# hybrid_lower_pcb3_1.net
KiCad netlist of a schematic drawn in EAGLE
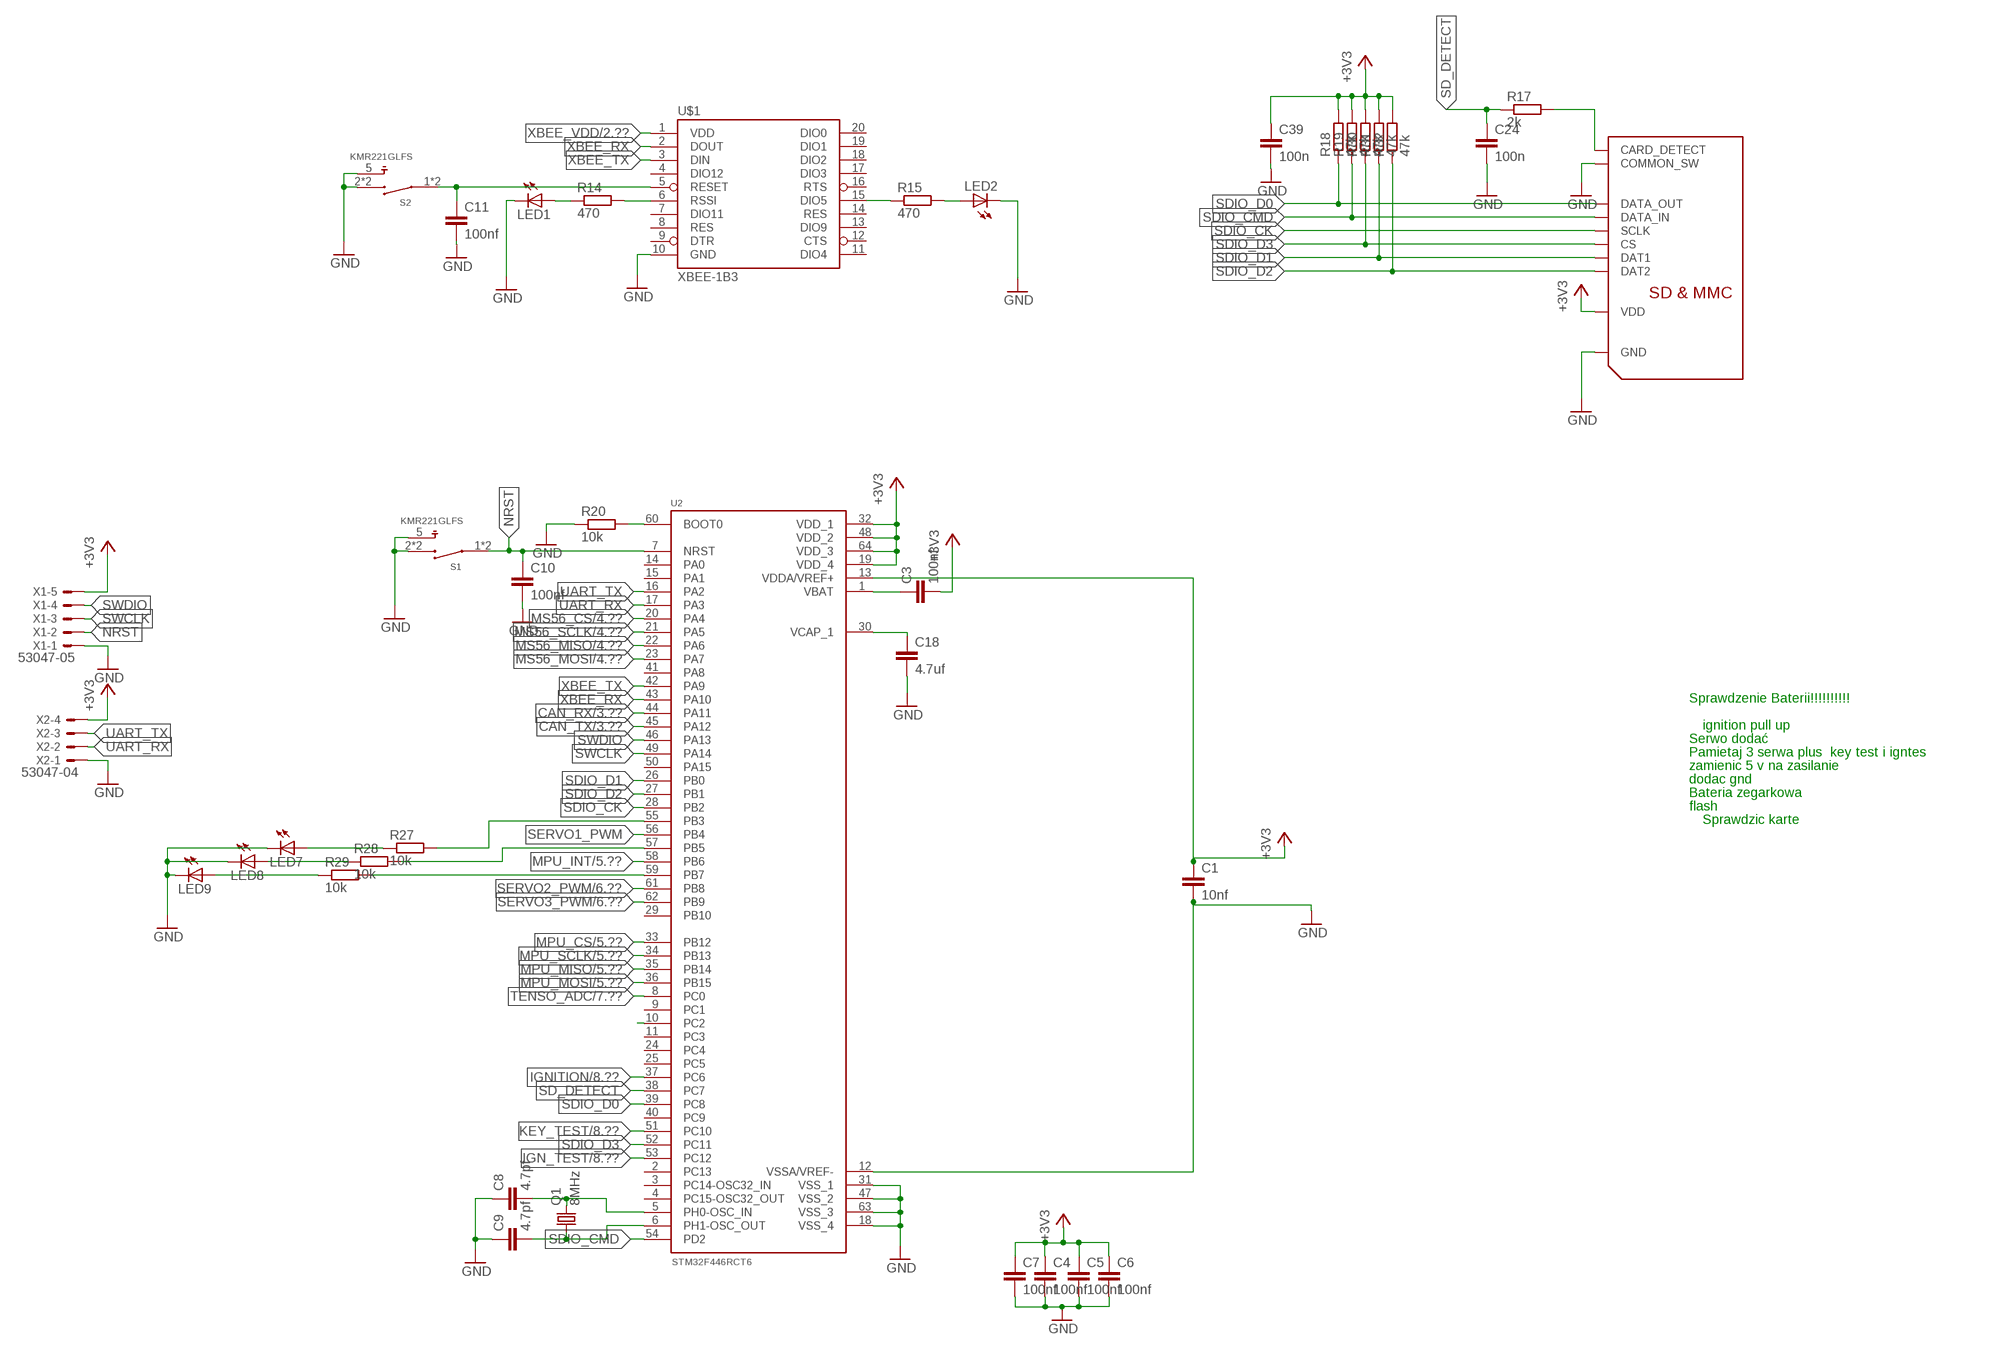
[diagram p0: schematic, sheet 1]
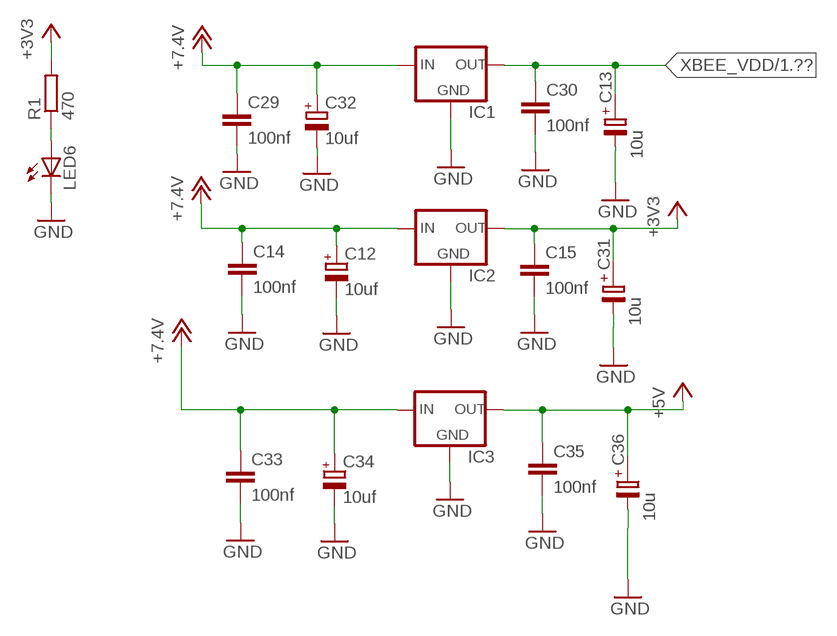
[diagram p1: schematic, sheet 2]
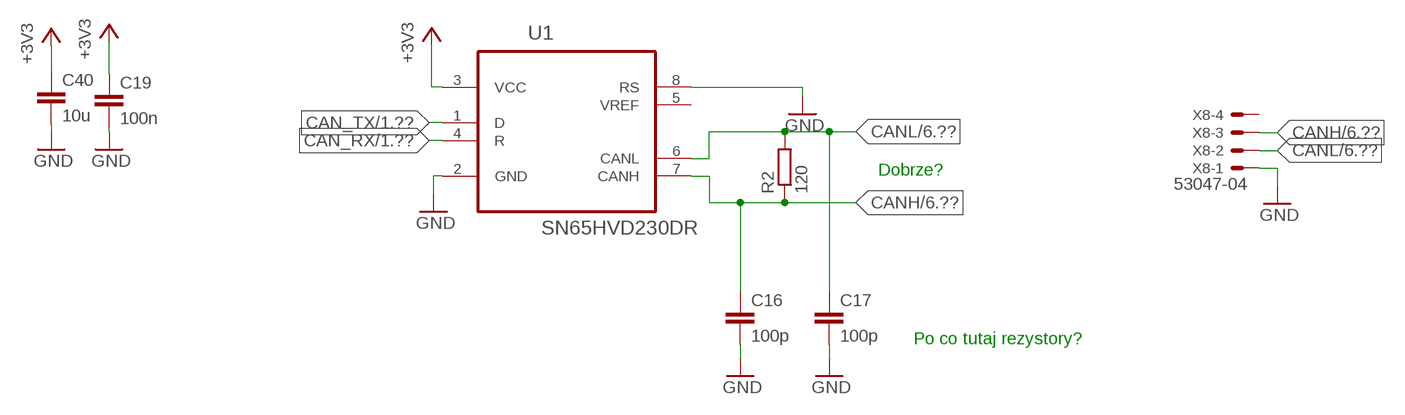
[diagram p2: schematic, sheet 3]
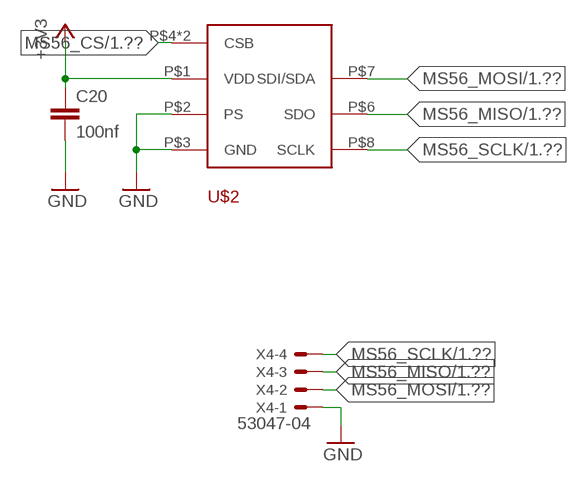
[diagram p3: schematic, sheet 4]
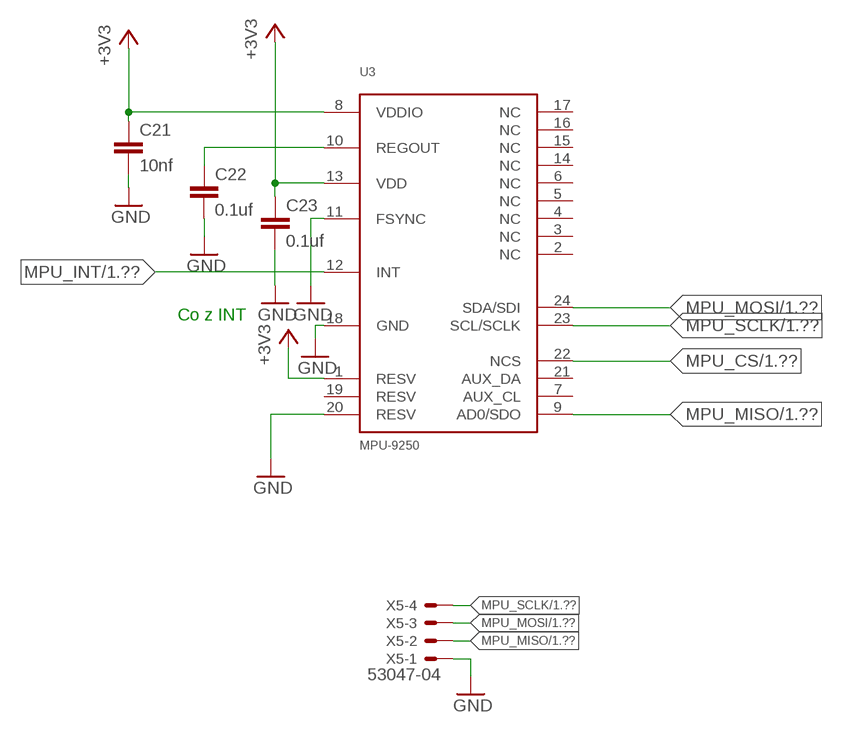
[diagram p4: schematic, sheet 5]
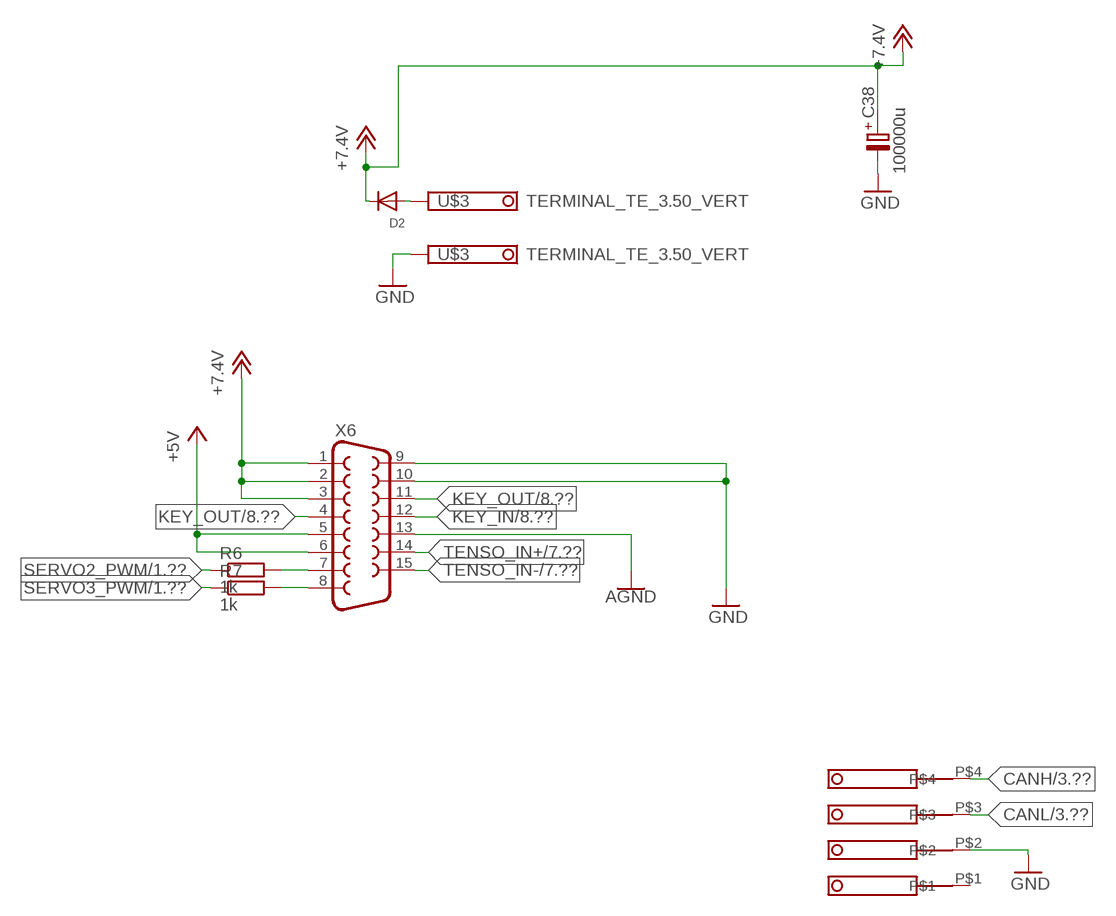
[diagram p5: schematic, sheet 6]
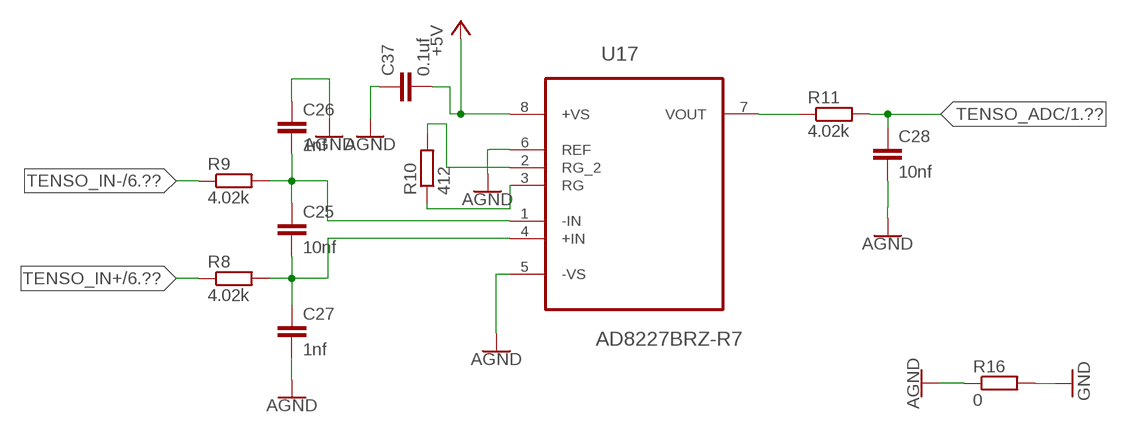
[diagram p6: schematic, sheet 7]
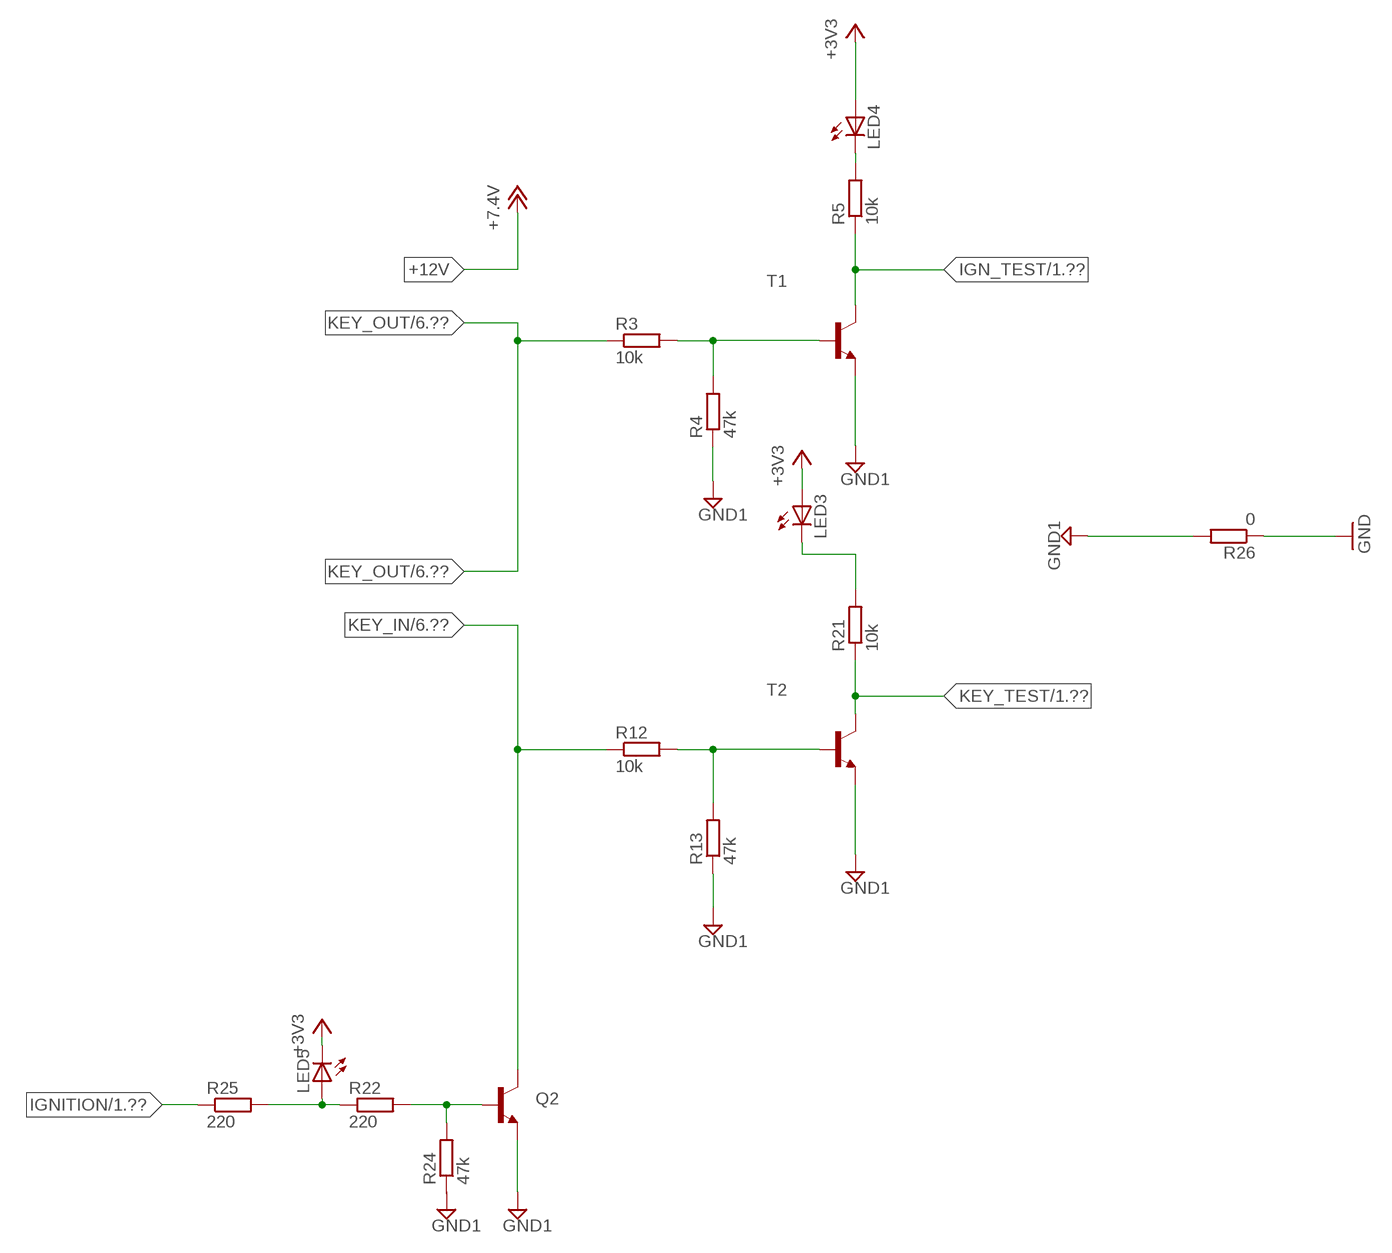
[diagram p7: schematic, sheet 8]

(export (version "E")
  (design (tool "Eeschema 10.0.6"))
  (components
    (comp (ref "LED3")
      (value "LED0603")
      (footprint "eagle-import:LED-0603")
      (libsource (lib "eagle-import") (part "LED0603"))
    )
    (comp (ref "LED4")
      (value "LED0603")
      (footprint "eagle-import:LED-0603")
      (libsource (lib "eagle-import") (part "LED0603"))
    )
    (comp (ref "LED5")
      (value "LED0603")
      (footprint "eagle-import:LED-0603")
      (libsource (lib "eagle-import") (part "LED0603"))
    )
    (comp (ref "Q2")
      (value "TRANSISTOR_NPNSOT23-3")
      (footprint "eagle-import:SOT23-3")
      (libsource (lib "eagle-import") (part "TRANSISTOR_NPNSOT23-3"))
    )
    (comp (ref "R3")
      (value "10k")
      (footprint "eagle-import:R0603")
      (libsource (lib "eagle-import") (part "R-EU_R0603"))
    )
    (comp (ref "R4")
      (value "47k")
      (footprint "eagle-import:R0603")
      (libsource (lib "eagle-import") (part "R-EU_R0603"))
    )
    (comp (ref "R5")
      (value "10k")
      (footprint "eagle-import:R0603")
      (libsource (lib "eagle-import") (part "R-EU_R0603"))
    )
    (comp (ref "R12")
      (value "10k")
      (footprint "eagle-import:R0603")
      (libsource (lib "eagle-import") (part "R-EU_R0603"))
    )
    (comp (ref "R13")
      (value "47k")
      (footprint "eagle-import:R0603")
      (libsource (lib "eagle-import") (part "R-EU_R0603"))
    )
    (comp (ref "R21")
      (value "10k")
      (footprint "eagle-import:R0603")
      (libsource (lib "eagle-import") (part "R-EU_R0603"))
    )
    (comp (ref "R22")
      (value "220")
      (footprint "eagle-import:R0603")
      (libsource (lib "eagle-import") (part "R-EU_R0603"))
    )
    (comp (ref "R24")
      (value "47k")
      (footprint "eagle-import:R0603")
      (libsource (lib "eagle-import") (part "R-EU_R0603"))
    )
    (comp (ref "R25")
      (value "220")
      (footprint "eagle-import:R0603")
      (libsource (lib "eagle-import") (part "R-EU_R0603"))
    )
    (comp (ref "R26")
      (value "0")
      (footprint "eagle-import:R0603")
      (libsource (lib "eagle-import") (part "R-EU_R0603"))
    )
    (comp (ref "T1")
      (value "BCW81-NPN-SOT23-BEC")
      (footprint "eagle-import:SOT23-BEC")
      (libsource (lib "eagle-import") (part "-NPN-SOT23-BECBCW81"))
    )
    (comp (ref "T2")
      (value "BCW81-NPN-SOT23-BEC")
      (footprint "eagle-import:SOT23-BEC")
      (libsource (lib "eagle-import") (part "-NPN-SOT23-BECBCW81"))
    )
    (comp (ref "C16")
      (value "100p")
      (footprint "eagle-import:C0603")
      (libsource (lib "eagle-import") (part "C-EUC0603"))
    )
    (comp (ref "C17")
      (value "100p")
      (footprint "eagle-import:C0603")
      (libsource (lib "eagle-import") (part "C-EUC0603"))
    )
    (comp (ref "C19")
      (value "100n")
      (footprint "eagle-import:C0603")
      (libsource (lib "eagle-import") (part "C-EUC0603"))
    )
    (comp (ref "C40")
      (value "10u")
      (footprint "eagle-import:C0805")
      (libsource (lib "eagle-import") (part "C-EUC0805"))
    )
    (comp (ref "R2")
      (value "120")
      (footprint "eagle-import:R0603")
      (libsource (lib "eagle-import") (part "R-EU_R0603"))
    )
    (comp (ref "U1")
      (value "SN65HVD230DR")
      (footprint "eagle-import:SOIC127P600X175-8N")
      (fields (field (name "MF") "Texas Instruments"))
      (libsource (lib "eagle-import") (part "SN65HVD230DR"))
    )
    (comp (ref "X8")
      (value "53047-04")
      (footprint "eagle-import:53047-04")
      (fields (field (name "MF") "WALDOM/MOLEX") (field (name "MPN") "53047-0410"))
      (libsource (lib "eagle-import") (part "53?-04047"))
    )
    (comp (ref "C38")
      (value "100000u")
      (footprint "eagle-import:TE-B-3528")
      (libsource (lib "eagle-import") (part "C-PR-SMD-TE-B"))
    )
    (comp (ref "D2")
      (value "DIODESOD-523")
      (footprint "eagle-import:SOD-523")
      (libsource (lib "eagle-import") (part "DIODESOD-523"))
    )
    (comp (ref "R6")
      (value "1k")
      (footprint "eagle-import:R0603")
      (libsource (lib "eagle-import") (part "R-EU_R0603"))
    )
    (comp (ref "R7")
      (value "1k")
      (footprint "eagle-import:R0603")
      (libsource (lib "eagle-import") (part "R-EU_R0603"))
    )
    (comp (ref "U$3")
      (value "TERMINAL_TE_3.50_VERT")
      (footprint "eagle-import:TE_3.5_TERMINAL_VERT")
      (libsource (lib "eagle-import") (part "TERMINAL_TE_3.50_VERT"))
    )
    (comp (ref "U$10")
      (value "39505-1005")
      (footprint "eagle-import:39505-1005")
      (libsource (lib "eagle-import") (part "39505-1005"))
    )
    (comp (ref "X6")
      (value "F15VP")
      (footprint "eagle-import:F15VP")
      (libsource (lib "eagle-import") (part "F15VP"))
    )
    (comp (ref "C21")
      (value "10nf")
      (footprint "eagle-import:C0603")
      (libsource (lib "eagle-import") (part "C-EUC0603"))
    )
    (comp (ref "C22")
      (value "0.1uf")
      (footprint "eagle-import:C0603")
      (libsource (lib "eagle-import") (part "C-EUC0603"))
    )
    (comp (ref "C23")
      (value "0.1uf")
      (footprint "eagle-import:C0603")
      (libsource (lib "eagle-import") (part "C-EUC0603"))
    )
    (comp (ref "U3")
      (value "MPU-9250")
      (footprint "eagle-import:MPU-9250")
      (fields (field (name "MF") "InvenSense"))
      (libsource (lib "eagle-import") (part "MPU-9250"))
    )
    (comp (ref "X5")
      (value "53047-04")
      (footprint "eagle-import:53047-04")
      (fields (field (name "MF") "WALDOM/MOLEX") (field (name "MPN") "53047-0410"))
      (libsource (lib "eagle-import") (part "53?-04047"))
    )
    (comp (ref "C20")
      (value "100nf")
      (footprint "eagle-import:C0603")
      (libsource (lib "eagle-import") (part "resistor_C-EUC0603"))
    )
    (comp (ref "U$2")
      (value "MS56XX")
      (footprint "eagle-import:MS56XX")
      (libsource (lib "eagle-import") (part "MS56XX"))
    )
    (comp (ref "X4")
      (value "53047-04")
      (footprint "eagle-import:53047-04")
      (fields (field (name "MF") "WALDOM/MOLEX") (field (name "MPN") "53047-0410"))
      (libsource (lib "eagle-import") (part "53?-04047"))
    )
    (comp (ref "C12")
      (value "10uf")
      (footprint "eagle-import:SANYO-OSCON_SMD_B6")
      (libsource (lib "eagle-import") (part "CPOL-EUSANYO_SMD_B6"))
    )
    (comp (ref "C13")
      (value "10u")
      (footprint "eagle-import:TE-B-3528")
      (libsource (lib "eagle-import") (part "C-PR-SMD-TE-B"))
    )
    (comp (ref "C14")
      (value "100nf")
      (footprint "eagle-import:C0603")
      (libsource (lib "eagle-import") (part "C-EUC0603"))
    )
    (comp (ref "C15")
      (value "100nf")
      (footprint "eagle-import:C0603")
      (libsource (lib "eagle-import") (part "C-EUC0603"))
    )
    (comp (ref "C29")
      (value "100nf")
      (footprint "eagle-import:C0603")
      (libsource (lib "eagle-import") (part "C-EUC0603"))
    )
    (comp (ref "C30")
      (value "100nf")
      (footprint "eagle-import:C0603")
      (libsource (lib "eagle-import") (part "C-EUC0603"))
    )
    (comp (ref "C31")
      (value "10u")
      (footprint "eagle-import:TE-B-3528")
      (libsource (lib "eagle-import") (part "C-PR-SMD-TE-B"))
    )
    (comp (ref "C32")
      (value "10uf")
      (footprint "eagle-import:SANYO-OSCON_SMD_B6")
      (libsource (lib "eagle-import") (part "CPOL-EUSANYO_SMD_B6"))
    )
    (comp (ref "C33")
      (value "100nf")
      (footprint "eagle-import:C0603")
      (libsource (lib "eagle-import") (part "C-EUC0603"))
    )
    (comp (ref "C34")
      (value "10uf")
      (footprint "eagle-import:SANYO-OSCON_SMD_B6")
      (libsource (lib "eagle-import") (part "CPOL-EUSANYO_SMD_B6"))
    )
    (comp (ref "C35")
      (value "100nf")
      (footprint "eagle-import:C0603")
      (libsource (lib "eagle-import") (part "C-EUC0603"))
    )
    (comp (ref "C36")
      (value "10u")
      (footprint "eagle-import:TE-B-3528")
      (libsource (lib "eagle-import") (part "C-PR-SMD-TE-B"))
    )
    (comp (ref "IC1")
      (value "LM1117")
      (footprint "eagle-import:SOT223")
      (libsource (lib "eagle-import") (part "LM1117"))
    )
    (comp (ref "IC2")
      (value "LM1117")
      (footprint "eagle-import:SOT223")
      (libsource (lib "eagle-import") (part "LM1117"))
    )
    (comp (ref "IC3")
      (value "LM1117")
      (footprint "eagle-import:SOT223")
      (libsource (lib "eagle-import") (part "LM1117"))
    )
    (comp (ref "LED6")
      (value "LED0603")
      (footprint "eagle-import:LED-0603")
      (libsource (lib "eagle-import") (part "LED0603"))
    )
    (comp (ref "R1")
      (value "470")
      (footprint "eagle-import:R0603")
      (libsource (lib "eagle-import") (part "resistor_R-EU_R0603"))
    )
    (comp (ref "C25")
      (value "10nf")
      (footprint "eagle-import:C0603")
      (libsource (lib "eagle-import") (part "C-EUC0603"))
    )
    (comp (ref "C26")
      (value "1nf")
      (footprint "eagle-import:C0603")
      (libsource (lib "eagle-import") (part "C-EUC0603"))
    )
    (comp (ref "C27")
      (value "1nf")
      (footprint "eagle-import:C0603")
      (libsource (lib "eagle-import") (part "C-EUC0603"))
    )
    (comp (ref "C28")
      (value "10nf")
      (footprint "eagle-import:C0603")
      (libsource (lib "eagle-import") (part "C-EUC0603"))
    )
    (comp (ref "C37")
      (value "0.1uf")
      (footprint "eagle-import:C0603")
      (libsource (lib "eagle-import") (part "C-EUC0603"))
    )
    (comp (ref "R8")
      (value "4.02k")
      (footprint "eagle-import:R0603")
      (libsource (lib "eagle-import") (part "R-EU_R0603"))
    )
    (comp (ref "R9")
      (value "4.02k")
      (footprint "eagle-import:R0603")
      (libsource (lib "eagle-import") (part "R-EU_R0603"))
    )
    (comp (ref "R10")
      (value "412")
      (footprint "eagle-import:R0805")
      (libsource (lib "eagle-import") (part "R-EU_R0805"))
    )
    (comp (ref "R11")
      (value "4.02k")
      (footprint "eagle-import:R0603")
      (libsource (lib "eagle-import") (part "R-EU_R0603"))
    )
    (comp (ref "R16")
      (value "0")
      (footprint "eagle-import:R0603")
      (libsource (lib "eagle-import") (part "resistor_R-EU_R0603"))
    )
    (comp (ref "U17")
      (value "AD8227BRZ-R7")
      (footprint "eagle-import:SOIC127P600X175-8N")
      (libsource (lib "eagle-import") (part "AD8227BRZ-R7"))
    )
    (comp (ref "C1")
      (value "10nf")
      (footprint "eagle-import:C0603")
      (libsource (lib "eagle-import") (part "C-EUC0603"))
    )
    (comp (ref "C3")
      (value "100nf")
      (footprint "eagle-import:C0603")
      (libsource (lib "eagle-import") (part "C-EUC0603"))
    )
    (comp (ref "C4")
      (value "100nf")
      (footprint "eagle-import:C0603")
      (libsource (lib "eagle-import") (part "C-EUC0603"))
    )
    (comp (ref "C5")
      (value "100nf")
      (footprint "eagle-import:C0603")
      (libsource (lib "eagle-import") (part "C-EUC0603"))
    )
    (comp (ref "C6")
      (value "100nf")
      (footprint "eagle-import:C0603")
      (libsource (lib "eagle-import") (part "C-EUC0603"))
    )
    (comp (ref "C7")
      (value "100nf")
      (footprint "eagle-import:C0603")
      (libsource (lib "eagle-import") (part "C-EUC0603"))
    )
    (comp (ref "C8")
      (value "4.7pf")
      (footprint "eagle-import:C0603")
      (libsource (lib "eagle-import") (part "C-EUC0603"))
    )
    (comp (ref "C9")
      (value "4.7pf")
      (footprint "eagle-import:C0603")
      (libsource (lib "eagle-import") (part "C-EUC0603"))
    )
    (comp (ref "C10")
      (value "100nf")
      (footprint "eagle-import:C0603")
      (libsource (lib "eagle-import") (part "C-EUC0603"))
    )
    (comp (ref "C11")
      (value "100nf")
      (footprint "eagle-import:C0603")
      (libsource (lib "eagle-import") (part "C-EUC0603"))
    )
    (comp (ref "C18")
      (value "4.7uf")
      (footprint "eagle-import:C0805")
      (libsource (lib "eagle-import") (part "rcl_334_C-EUC0805"))
    )
    (comp (ref "C24")
      (value "100n")
      (footprint "eagle-import:C0603K")
      (libsource (lib "eagle-import") (part "C-EUC0603K"))
    )
    (comp (ref "C39")
      (value "100n")
      (footprint "eagle-import:C0603K")
      (libsource (lib "eagle-import") (part "C-EUC0603K"))
    )
    (comp (ref "LED1")
      (value "LED0603")
      (footprint "eagle-import:LED-0603")
      (libsource (lib "eagle-import") (part "LED0603"))
    )
    (comp (ref "LED2")
      (value "LED0603")
      (footprint "eagle-import:LED-0603")
      (libsource (lib "eagle-import") (part "LED0603"))
    )
    (comp (ref "LED7")
      (value "LED0603")
      (footprint "eagle-import:LED-0603")
      (libsource (lib "eagle-import") (part "LED0603"))
    )
    (comp (ref "LED8")
      (value "LED0603")
      (footprint "eagle-import:LED-0603")
      (libsource (lib "eagle-import") (part "LED0603"))
    )
    (comp (ref "LED9")
      (value "LED0603")
      (footprint "eagle-import:LED-0603")
      (libsource (lib "eagle-import") (part "LED0603"))
    )
    (comp (ref "Q1")
      (value "8MHz")
      (footprint "eagle-import:CTS406")
      (libsource (lib "eagle-import") (part "CRYSTALCTS406"))
    )
    (comp (ref "R14")
      (value "470")
      (footprint "eagle-import:R0603")
      (libsource (lib "eagle-import") (part "R-EU_R0603"))
    )
    (comp (ref "R15")
      (value "470")
      (footprint "eagle-import:R0603")
      (libsource (lib "eagle-import") (part "R-EU_R0603"))
    )
    (comp (ref "R17")
      (value "2k")
      (footprint "eagle-import:R0603")
      (libsource (lib "eagle-import") (part "R-EU_R0603"))
    )
    (comp (ref "R18")
      (value "47k")
      (footprint "eagle-import:R0603")
      (libsource (lib "eagle-import") (part "R-EU_R0603"))
    )
    (comp (ref "R19")
      (value "47k")
      (footprint "eagle-import:R0603")
      (libsource (lib "eagle-import") (part "R-EU_R0603"))
    )
    (comp (ref "R20")
      (value "10k")
      (footprint "eagle-import:R0603")
      (libsource (lib "eagle-import") (part "resistor_R-EU_R0603"))
    )
    (comp (ref "R27")
      (value "10k")
      (footprint "eagle-import:R0603")
      (libsource (lib "eagle-import") (part "resistor_R-EU_R0603"))
    )
    (comp (ref "R28")
      (value "10k")
      (footprint "eagle-import:R0603")
      (libsource (lib "eagle-import") (part "resistor_R-EU_R0603"))
    )
    (comp (ref "R29")
      (value "10k")
      (footprint "eagle-import:R0603")
      (libsource (lib "eagle-import") (part "resistor_R-EU_R0603"))
    )
    (comp (ref "R30")
      (value "47k")
      (footprint "eagle-import:R0603")
      (libsource (lib "eagle-import") (part "R-EU_R0603"))
    )
    (comp (ref "R31")
      (value "47k")
      (footprint "eagle-import:R0603")
      (libsource (lib "eagle-import") (part "R-EU_R0603"))
    )
    (comp (ref "R32")
      (value "47k")
      (footprint "eagle-import:R0603")
      (libsource (lib "eagle-import") (part "R-EU_R0603"))
    )
    (comp (ref "S1")
      (value "KMR221GLFS")
      (footprint "eagle-import:SW_KMR221GLFS")
      (fields (field (name "MF") "C&K Components"))
      (libsource (lib "eagle-import") (part "KMR221GLFS"))
    )
    (comp (ref "S2")
      (value "KMR221GLFS")
      (footprint "eagle-import:SW_KMR221GLFS")
      (fields (field (name "MF") "C&K Components"))
      (libsource (lib "eagle-import") (part "KMR221GLFS"))
    )
    (comp (ref "U$1")
      (value "XBEE-1B3")
      (footprint "eagle-import:XBEE-SMD")
      (libsource (lib "eagle-import") (part "XBEE-1B3"))
    )
    (comp (ref "U$11")
      (value "MOLEX_MICRO_SD_503182-1853")
      (footprint "eagle-import:MOLEX_MICRO_SD_503182-1853")
      (libsource (lib "eagle-import") (part "MOLEX_MICRO_SD_503182-1853"))
    )
    (comp (ref "U2")
      (value "STM32F446RCT6")
      (footprint "eagle-import:QFP50P1200X1200X160-64N")
      (fields (field (name "MF") "STMicroelectronics"))
      (libsource (lib "eagle-import") (part "STM32F446RCT6"))
    )
    (comp (ref "X1")
      (value "53047-05")
      (footprint "eagle-import:53047-05")
      (fields (field (name "MF") "MOLEX") (field (name "MPN") "53047-0510"))
      (libsource (lib "eagle-import") (part "53?-05047"))
    )
    (comp (ref "X2")
      (value "53047-04")
      (footprint "eagle-import:53047-04")
      (fields (field (name "MF") "WALDOM/MOLEX") (field (name "MPN") "53047-0410"))
      (libsource (lib "eagle-import") (part "53?-04047"))
    )
  )
  (nets
    (net (code "1") (name "+3V3") (class "Default")
      (node (ref "C1") (pin "1") (pinfunction "1_1") (pintype "passive"))
      (node (ref "C15") (pin "1") (pinfunction "1_1") (pintype "passive"))
      (node (ref "C19") (pin "1") (pinfunction "1_1") (pintype "passive"))
      (node (ref "C20") (pin "1") (pinfunction "1_1") (pintype "passive"))
      (node (ref "C21") (pin "1") (pinfunction "1_1") (pintype "passive"))
      (node (ref "C23") (pin "1") (pinfunction "1_1") (pintype "passive"))
      (node (ref "C3") (pin "2") (pinfunction "2_2") (pintype "passive"))
      (node (ref "C31") (pin "+") (pinfunction "+_+") (pintype "passive"))
      (node (ref "C39") (pin "1") (pinfunction "1_1") (pintype "passive"))
      (node (ref "C4") (pin "1") (pinfunction "1_1") (pintype "passive"))
      (node (ref "C40") (pin "1") (pinfunction "1_1") (pintype "passive"))
      (node (ref "C5") (pin "1") (pinfunction "1_1") (pintype "passive"))
      (node (ref "C6") (pin "1") (pinfunction "1_1") (pintype "passive"))
      (node (ref "C7") (pin "1") (pinfunction "1_1") (pintype "passive"))
      (node (ref "IC2") (pin "2") (pinfunction "OUT_2") (pintype "passive"))
      (node (ref "LED3") (pin "A") (pinfunction "A_A") (pintype "passive"))
      (node (ref "LED4") (pin "A") (pinfunction "A_A") (pintype "passive"))
      (node (ref "LED5") (pin "C") (pinfunction "C_C") (pintype "passive"))
      (node (ref "R1") (pin "2") (pinfunction "2_2") (pintype "passive"))
      (node (ref "R18") (pin "2") (pinfunction "2_2") (pintype "passive"))
      (node (ref "R19") (pin "2") (pinfunction "2_2") (pintype "passive"))
      (node (ref "R30") (pin "2") (pinfunction "2_2") (pintype "passive"))
      (node (ref "R31") (pin "2") (pinfunction "2_2") (pintype "passive"))
      (node (ref "R32") (pin "2") (pinfunction "2_2") (pintype "passive"))
      (node (ref "U$11") (pin "PIN4") (pinfunction "VDD_PIN4") (pintype "power_in"))
      (node (ref "U$2") (pin "P$1") (pinfunction "VDD_P$1") (pintype "bidirectional"))
      (node (ref "U1") (pin "3") (pinfunction "VCC_3") (pintype "power_in"))
      (node (ref "U2") (pin "13") (pinfunction "VDDA/VREF+_13") (pintype "power_in"))
      (node (ref "U2") (pin "19") (pinfunction "VDD_4_19") (pintype "power_in"))
      (node (ref "U2") (pin "32") (pinfunction "VDD_1_32") (pintype "power_in"))
      (node (ref "U2") (pin "48") (pinfunction "VDD_2_48") (pintype "power_in"))
      (node (ref "U2") (pin "64") (pinfunction "VDD_3_64") (pintype "power_in"))
      (node (ref "U3") (pin "1") (pinfunction "RESV_1") (pintype "bidirectional"))
      (node (ref "U3") (pin "13") (pinfunction "VDD_13") (pintype "bidirectional"))
      (node (ref "U3") (pin "8") (pinfunction "VDDIO_8") (pintype "bidirectional"))
      (node (ref "X1") (pin "5") (pinfunction "S_5") (pintype "passive"))
      (node (ref "X2") (pin "4") (pinfunction "S_4") (pintype "passive"))
    )
    (net (code "2") (name "+5V") (class "Default")
      (node (ref "C35") (pin "1") (pinfunction "1_1") (pintype "passive"))
      (node (ref "C36") (pin "+") (pinfunction "+_+") (pintype "passive"))
      (node (ref "C37") (pin "2") (pinfunction "2_2") (pintype "passive"))
      (node (ref "IC3") (pin "2") (pinfunction "OUT_2") (pintype "passive"))
      (node (ref "U17") (pin "8") (pinfunction "+VS_8") (pintype "power_in"))
      (node (ref "X6") (pin "5") (pinfunction "5_5") (pintype "passive"))
      (node (ref "X6") (pin "6") (pinfunction "6_6") (pintype "passive"))
    )
    (net (code "3") (name "+12V") (class "Default")
      (node (ref "C12") (pin "+") (pinfunction "+_+") (pintype "passive"))
      (node (ref "C14") (pin "1") (pinfunction "1_1") (pintype "passive"))
      (node (ref "C29") (pin "1") (pinfunction "1_1") (pintype "passive"))
      (node (ref "C32") (pin "+") (pinfunction "+_+") (pintype "passive"))
      (node (ref "C33") (pin "1") (pinfunction "1_1") (pintype "passive"))
      (node (ref "C34") (pin "+") (pinfunction "+_+") (pintype "passive"))
      (node (ref "C38") (pin "+") (pinfunction "+_+") (pintype "passive"))
      (node (ref "D2") (pin "K") (pinfunction "C_K") (pintype "passive"))
      (node (ref "IC1") (pin "3") (pinfunction "IN_3") (pintype "input"))
      (node (ref "IC2") (pin "3") (pinfunction "IN_3") (pintype "input"))
      (node (ref "IC3") (pin "3") (pinfunction "IN_3") (pintype "input"))
      (node (ref "X6") (pin "1") (pinfunction "1_1") (pintype "passive"))
      (node (ref "X6") (pin "2") (pinfunction "2_2") (pintype "passive"))
      (node (ref "X6") (pin "3") (pinfunction "3_3") (pintype "passive"))
    )
    (net (code "4") (name "AGND") (class "Default")
      (node (ref "C26") (pin "1") (pinfunction "1_1") (pintype "passive"))
      (node (ref "C27") (pin "2") (pinfunction "2_2") (pintype "passive"))
      (node (ref "C28") (pin "2") (pinfunction "2_2") (pintype "passive"))
      (node (ref "C37") (pin "1") (pinfunction "1_1") (pintype "passive"))
      (node (ref "R16") (pin "1") (pinfunction "1_1") (pintype "passive"))
      (node (ref "U17") (pin "5") (pinfunction "-VS_5") (pintype "power_in"))
      (node (ref "U17") (pin "6") (pinfunction "REF_6") (pintype "input"))
      (node (ref "X6") (pin "13") (pinfunction "13_13") (pintype "passive"))
    )
    (net (code "5") (name "CANH") (class "Default")
      (node (ref "C16") (pin "1") (pinfunction "1_1") (pintype "passive"))
      (node (ref "R2") (pin "1") (pinfunction "1_1") (pintype "passive"))
      (node (ref "U$10") (pin "P$4") (pinfunction "P$4_P$4") (pintype "bidirectional"))
      (node (ref "U1") (pin "7") (pinfunction "CANH_7") (pintype "output"))
      (node (ref "X8") (pin "3") (pinfunction "S_3") (pintype "passive"))
    )
    (net (code "6") (name "CANL") (class "Default")
      (node (ref "C17") (pin "1") (pinfunction "1_1") (pintype "passive"))
      (node (ref "R2") (pin "2") (pinfunction "2_2") (pintype "passive"))
      (node (ref "U$10") (pin "P$3") (pinfunction "P$3_P$3") (pintype "bidirectional"))
      (node (ref "U1") (pin "6") (pinfunction "CANL_6") (pintype "output"))
      (node (ref "X8") (pin "2") (pinfunction "S_2") (pintype "passive"))
    )
    (net (code "7") (name "CAN_RX") (class "Default")
      (node (ref "U1") (pin "4") (pinfunction "R_4") (pintype "output"))
      (node (ref "U2") (pin "44") (pinfunction "PA11_44") (pintype "bidirectional"))
    )
    (net (code "8") (name "CAN_TX") (class "Default")
      (node (ref "U1") (pin "1") (pinfunction "D_1") (pintype "input"))
      (node (ref "U2") (pin "45") (pinfunction "PA12_45") (pintype "bidirectional"))
    )
    (net (code "9") (name "GND") (class "Default")
      (node (ref "C1") (pin "2") (pinfunction "2_2") (pintype "passive"))
      (node (ref "C10") (pin "2") (pinfunction "2_2") (pintype "passive"))
      (node (ref "C11") (pin "2") (pinfunction "2_2") (pintype "passive"))
      (node (ref "C12") (pin "-") (pinfunction "-_-") (pintype "passive"))
      (node (ref "C13") (pin "-") (pinfunction "-_-") (pintype "passive"))
      (node (ref "C14") (pin "2") (pinfunction "2_2") (pintype "passive"))
      (node (ref "C15") (pin "2") (pinfunction "2_2") (pintype "passive"))
      (node (ref "C16") (pin "2") (pinfunction "2_2") (pintype "passive"))
      (node (ref "C17") (pin "2") (pinfunction "2_2") (pintype "passive"))
      (node (ref "C18") (pin "2") (pinfunction "2_2") (pintype "passive"))
      (node (ref "C19") (pin "2") (pinfunction "2_2") (pintype "passive"))
      (node (ref "C20") (pin "2") (pinfunction "2_2") (pintype "passive"))
      (node (ref "C21") (pin "2") (pinfunction "2_2") (pintype "passive"))
      (node (ref "C22") (pin "2") (pinfunction "2_2") (pintype "passive"))
      (node (ref "C23") (pin "2") (pinfunction "2_2") (pintype "passive"))
      (node (ref "C24") (pin "2") (pinfunction "2_2") (pintype "passive"))
      (node (ref "C29") (pin "2") (pinfunction "2_2") (pintype "passive"))
      (node (ref "C30") (pin "2") (pinfunction "2_2") (pintype "passive"))
      (node (ref "C31") (pin "-") (pinfunction "-_-") (pintype "passive"))
      (node (ref "C32") (pin "-") (pinfunction "-_-") (pintype "passive"))
      (node (ref "C33") (pin "2") (pinfunction "2_2") (pintype "passive"))
      (node (ref "C34") (pin "-") (pinfunction "-_-") (pintype "passive"))
      (node (ref "C35") (pin "2") (pinfunction "2_2") (pintype "passive"))
      (node (ref "C36") (pin "-") (pinfunction "-_-") (pintype "passive"))
      (node (ref "C38") (pin "-") (pinfunction "-_-") (pintype "passive"))
      (node (ref "C39") (pin "2") (pinfunction "2_2") (pintype "passive"))
      (node (ref "C4") (pin "2") (pinfunction "2_2") (pintype "passive"))
      (node (ref "C40") (pin "2") (pinfunction "2_2") (pintype "passive"))
      (node (ref "C5") (pin "2") (pinfunction "2_2") (pintype "passive"))
      (node (ref "C6") (pin "2") (pinfunction "2_2") (pintype "passive"))
      (node (ref "C7") (pin "2") (pinfunction "2_2") (pintype "passive"))
      (node (ref "C8") (pin "1") (pinfunction "1_1") (pintype "passive"))
      (node (ref "C9") (pin "1") (pinfunction "1_1") (pintype "passive"))
      (node (ref "IC1") (pin "1") (pinfunction "GND_1") (pintype "input"))
      (node (ref "IC2") (pin "1") (pinfunction "GND_1") (pintype "input"))
      (node (ref "IC3") (pin "1") (pinfunction "GND_1") (pintype "input"))
      (node (ref "LED1") (pin "C") (pinfunction "C_C") (pintype "passive"))
      (node (ref "LED2") (pin "C") (pinfunction "C_C") (pintype "passive"))
      (node (ref "LED6") (pin "C") (pinfunction "C_C") (pintype "passive"))
      (node (ref "LED7") (pin "C") (pinfunction "C_C") (pintype "passive"))
      (node (ref "LED8") (pin "C") (pinfunction "C_C") (pintype "passive"))
      (node (ref "LED9") (pin "C") (pinfunction "C_C") (pintype "passive"))
      (node (ref "R16") (pin "2") (pinfunction "2_2") (pintype "passive"))
      (node (ref "R20") (pin "1") (pinfunction "1_1") (pintype "passive"))
      (node (ref "R26") (pin "1") (pinfunction "1_1") (pintype "passive"))
      (node (ref "S1") (pin "2") (pinfunction "3_2") (pintype "passive"))
      (node (ref "S1") (pin "3") (pinfunction "3_3") (pintype "passive"))
      (node (ref "S1") (pin "5") (pinfunction "5_5") (pintype "passive"))
      (node (ref "S2") (pin "2") (pinfunction "3_2") (pintype "passive"))
      (node (ref "S2") (pin "3") (pinfunction "3_3") (pintype "passive"))
      (node (ref "S2") (pin "5") (pinfunction "5_5") (pintype "passive"))
      (node (ref "U$1") (pin "10") (pinfunction "GND_10") (pintype "power_in"))
      (node (ref "U$10") (pin "P$2") (pinfunction "P$2_P$2") (pintype "bidirectional"))
      (node (ref "U$11") (pin "DETECT_GND") (pinfunction "COMMON_SW_DETECT_GND") (pintype "passive"))
      (node (ref "U$11") (pin "PIN6") (pinfunction "GND_PIN6") (pintype "power_in"))
      (node (ref "U$2") (pin "P$2") (pinfunction "PS_P$2") (pintype "bidirectional"))
      (node (ref "U$2") (pin "P$3") (pinfunction "GND_P$3") (pintype "bidirectional"))
      (node (ref "U$3") (pin "P$2") (pinfunction "K1_P$2") (pintype "passive"))
      (node (ref "U1") (pin "2") (pinfunction "GND_2") (pintype "passive"))
      (node (ref "U1") (pin "8") (pinfunction "RS_8") (pintype "input"))
      (node (ref "U2") (pin "12") (pinfunction "VSSA/VREF-_12") (pintype "power_in"))
      (node (ref "U2") (pin "18") (pinfunction "VSS_4_18") (pintype "power_in"))
      (node (ref "U2") (pin "31") (pinfunction "VSS_1_31") (pintype "power_in"))
      (node (ref "U2") (pin "47") (pinfunction "VSS_2_47") (pintype "power_in"))
      (node (ref "U2") (pin "63") (pinfunction "VSS_3_63") (pintype "power_in"))
      (node (ref "U3") (pin "11") (pinfunction "FSYNC_11") (pintype "bidirectional"))
      (node (ref "U3") (pin "18") (pinfunction "GND_18") (pintype "bidirectional"))
      (node (ref "U3") (pin "20") (pinfunction "RESV_20") (pintype "bidirectional"))
      (node (ref "X1") (pin "1") (pinfunction "S_1") (pintype "passive"))
      (node (ref "X2") (pin "1") (pinfunction "S_1") (pintype "passive"))
      (node (ref "X4") (pin "1") (pinfunction "S_1") (pintype "passive"))
      (node (ref "X5") (pin "1") (pinfunction "S_1") (pintype "passive"))
      (node (ref "X6") (pin "10") (pinfunction "10_10") (pintype "passive"))
      (node (ref "X6") (pin "9") (pinfunction "9_9") (pintype "passive"))
      (node (ref "X8") (pin "1") (pinfunction "S_1") (pintype "passive"))
    )
    (net (code "10") (name "GND1") (class "Default")
      (node (ref "Q2") (pin "2") (pinfunction "E_2") (pintype "passive"))
      (node (ref "R13") (pin "1") (pinfunction "1_1") (pintype "passive"))
      (node (ref "R26") (pin "2") (pinfunction "2_2") (pintype "passive"))
      (node (ref "R4") (pin "1") (pinfunction "1_1") (pintype "passive"))
      (node (ref "T1") (pin "E") (pinfunction "E_E") (pintype "passive"))
      (node (ref "T2") (pin "E") (pinfunction "E_E") (pintype "passive"))
    )
    (net (code "11") (name "IGNITION") (class "Default")
      (node (ref "R25") (pin "1") (pinfunction "1_1") (pintype "passive"))
      (node (ref "U2") (pin "37") (pinfunction "PC6_37") (pintype "bidirectional"))
    )
    (net (code "12") (name "IGN_TEST") (class "Default")
      (node (ref "R5") (pin "1") (pinfunction "1_1") (pintype "passive"))
      (node (ref "T1") (pin "C") (pinfunction "C_C") (pintype "passive"))
      (node (ref "U2") (pin "53") (pinfunction "PC12_53") (pintype "bidirectional"))
    )
    (net (code "13") (name "KEY_IN") (class "Default")
      (node (ref "Q2") (pin "3") (pinfunction "C_3") (pintype "passive"))
      (node (ref "R12") (pin "1") (pinfunction "1_1") (pintype "passive"))
      (node (ref "X6") (pin "12") (pinfunction "12_12") (pintype "passive"))
    )
    (net (code "14") (name "KEY_OUT") (class "Default")
      (node (ref "R3") (pin "1") (pinfunction "1_1") (pintype "passive"))
      (node (ref "X6") (pin "11") (pinfunction "11_11") (pintype "passive"))
      (node (ref "X6") (pin "4") (pinfunction "4_4") (pintype "passive"))
    )
    (net (code "15") (name "KEY_TEST") (class "Default")
      (node (ref "R21") (pin "1") (pinfunction "1_1") (pintype "passive"))
      (node (ref "T2") (pin "C") (pinfunction "C_C") (pintype "passive"))
      (node (ref "U2") (pin "51") (pinfunction "PC10_51") (pintype "bidirectional"))
    )
    (net (code "16") (name "MPU_CS") (class "Default")
      (node (ref "U2") (pin "33") (pinfunction "PB12_33") (pintype "bidirectional"))
      (node (ref "U3") (pin "22") (pinfunction "NCS_22") (pintype "bidirectional"))
    )
    (net (code "17") (name "MPU_INT") (class "Default")
      (node (ref "U2") (pin "58") (pinfunction "PB6_58") (pintype "bidirectional"))
      (node (ref "U3") (pin "12") (pinfunction "INT_12") (pintype "bidirectional"))
    )
    (net (code "18") (name "MPU_MISO") (class "Default")
      (node (ref "U2") (pin "35") (pinfunction "PB14_35") (pintype "bidirectional"))
      (node (ref "U3") (pin "9") (pinfunction "AD0/SDO_9") (pintype "bidirectional"))
      (node (ref "X5") (pin "2") (pinfunction "S_2") (pintype "passive"))
    )
    (net (code "19") (name "MPU_MOSI") (class "Default")
      (node (ref "U2") (pin "36") (pinfunction "PB15_36") (pintype "bidirectional"))
      (node (ref "U3") (pin "24") (pinfunction "SDA/SDI_24") (pintype "bidirectional"))
      (node (ref "X5") (pin "3") (pinfunction "S_3") (pintype "passive"))
    )
    (net (code "20") (name "MPU_SCLK") (class "Default")
      (node (ref "U2") (pin "34") (pinfunction "PB13_34") (pintype "bidirectional"))
      (node (ref "U3") (pin "23") (pinfunction "SCL/SCLK_23") (pintype "bidirectional"))
      (node (ref "X5") (pin "4") (pinfunction "S_4") (pintype "passive"))
    )
    (net (code "21") (name "MS56_CS") (class "Default")
      (node (ref "U$2") (pin "P$4") (pinfunction "CSB_P$4") (pintype "bidirectional"))
      (node (ref "U$2") (pin "P$5") (pinfunction "CSB_P$5") (pintype "bidirectional"))
      (node (ref "U2") (pin "20") (pinfunction "PA4_20") (pintype "bidirectional"))
    )
    (net (code "22") (name "MS56_MISO") (class "Default")
      (node (ref "U$2") (pin "P$6") (pinfunction "SDO_P$6") (pintype "bidirectional"))
      (node (ref "U2") (pin "22") (pinfunction "PA6_22") (pintype "bidirectional"))
      (node (ref "X4") (pin "3") (pinfunction "S_3") (pintype "passive"))
    )
    (net (code "23") (name "MS56_MOSI") (class "Default")
      (node (ref "U$2") (pin "P$7") (pinfunction "SDI/SDA_P$7") (pintype "bidirectional"))
      (node (ref "U2") (pin "23") (pinfunction "PA7_23") (pintype "bidirectional"))
      (node (ref "X4") (pin "2") (pinfunction "S_2") (pintype "passive"))
    )
    (net (code "24") (name "MS56_SCLK") (class "Default")
      (node (ref "U$2") (pin "P$8") (pinfunction "SCLK_P$8") (pintype "bidirectional"))
      (node (ref "U2") (pin "21") (pinfunction "PA5_21") (pintype "bidirectional"))
      (node (ref "X4") (pin "4") (pinfunction "S_4") (pintype "passive"))
    )
    (net (code "25") (name "NRST") (class "Default")
      (node (ref "C10") (pin "1") (pinfunction "1_1") (pintype "passive"))
      (node (ref "S1") (pin "1") (pinfunction "1_1") (pintype "passive"))
      (node (ref "S1") (pin "4") (pinfunction "1_4") (pintype "passive"))
      (node (ref "U2") (pin "7") (pinfunction "NRST_7") (pintype "bidirectional"))
      (node (ref "X1") (pin "2") (pinfunction "S_2") (pintype "passive"))
    )
    (net (code "26") (name "Net-(LED1-PadA)") (class "Default")
      (node (ref "LED1") (pin "A") (pinfunction "A_A") (pintype "passive"))
      (node (ref "R14") (pin "1") (pinfunction "1_1") (pintype "passive"))
    )
    (net (code "27") (name "Net-(LED2-PadA)") (class "Default")
      (node (ref "LED2") (pin "A") (pinfunction "A_A") (pintype "passive"))
      (node (ref "R15") (pin "2") (pinfunction "2_2") (pintype "passive"))
    )
    (net (code "28") (name "Net-(LED3-PadC)") (class "Default")
      (node (ref "LED3") (pin "C") (pinfunction "C_C") (pintype "passive"))
      (node (ref "R21") (pin "2") (pinfunction "2_2") (pintype "passive"))
    )
    (net (code "29") (name "Net-(LED4-PadC)") (class "Default")
      (node (ref "LED4") (pin "C") (pinfunction "C_C") (pintype "passive"))
      (node (ref "R5") (pin "2") (pinfunction "2_2") (pintype "passive"))
    )
    (net (code "30") (name "Net-(LED5-PadA)") (class "Default")
      (node (ref "LED5") (pin "A") (pinfunction "A_A") (pintype "passive"))
      (node (ref "R22") (pin "1") (pinfunction "1_1") (pintype "passive"))
      (node (ref "R25") (pin "2") (pinfunction "2_2") (pintype "passive"))
    )
    (net (code "31") (name "Net-(LED6-PadA)") (class "Default")
      (node (ref "LED6") (pin "A") (pinfunction "A_A") (pintype "passive"))
      (node (ref "R1") (pin "1") (pinfunction "1_1") (pintype "passive"))
    )
    (net (code "32") (name "Net-(LED7-PadA)") (class "Default")
      (node (ref "LED7") (pin "A") (pinfunction "A_A") (pintype "passive"))
      (node (ref "R27") (pin "1") (pinfunction "1_1") (pintype "passive"))
    )
    (net (code "33") (name "Net-(LED8-PadA)") (class "Default")
      (node (ref "LED8") (pin "A") (pinfunction "A_A") (pintype "passive"))
      (node (ref "R28") (pin "1") (pinfunction "1_1") (pintype "passive"))
    )
    (net (code "34") (name "Net-(LED9-PadA)") (class "Default")
      (node (ref "LED9") (pin "A") (pinfunction "A_A") (pintype "passive"))
      (node (ref "R29") (pin "1") (pinfunction "1_1") (pintype "passive"))
    )
    (net (code "35") (name "Net-(Q1-2)") (class "Default")
      (node (ref "C8") (pin "2") (pinfunction "2_2") (pintype "passive"))
      (node (ref "Q1") (pin "3") (pinfunction "2_3") (pintype "passive"))
      (node (ref "U2") (pin "5") (pinfunction "PH0-OSC_IN_5") (pintype "bidirectional"))
    )
    (net (code "36") (name "Net-(Q2-B)") (class "Default")
      (node (ref "Q2") (pin "1") (pinfunction "B_1") (pintype "passive"))
      (node (ref "R22") (pin "2") (pinfunction "2_2") (pintype "passive"))
      (node (ref "R24") (pin "2") (pinfunction "2_2") (pintype "passive"))
    )
    (net (code "37") (name "Net-(R3-Pad2)") (class "Default")
      (node (ref "R3") (pin "2") (pinfunction "2_2") (pintype "passive"))
      (node (ref "R4") (pin "2") (pinfunction "2_2") (pintype "passive"))
      (node (ref "T1") (pin "B") (pinfunction "B_B") (pintype "passive"))
    )
    (net (code "38") (name "Net-(R6-Pad2)") (class "Default")
      (node (ref "R6") (pin "2") (pinfunction "2_2") (pintype "passive"))
      (node (ref "X6") (pin "7") (pinfunction "7_7") (pintype "passive"))
    )
    (net (code "39") (name "Net-(R7-Pad2)") (class "Default")
      (node (ref "R7") (pin "2") (pinfunction "2_2") (pintype "passive"))
      (node (ref "X6") (pin "8") (pinfunction "8_8") (pintype "passive"))
    )
    (net (code "40") (name "Net-(R12-Pad2)") (class "Default")
      (node (ref "R12") (pin "2") (pinfunction "2_2") (pintype "passive"))
      (node (ref "R13") (pin "2") (pinfunction "2_2") (pintype "passive"))
      (node (ref "T2") (pin "B") (pinfunction "B_B") (pintype "passive"))
    )
    (net (code "41") (name "Net-(U$1-DIO5)") (class "Default")
      (node (ref "R15") (pin "1") (pinfunction "1_1") (pintype "passive"))
      (node (ref "U$1") (pin "15") (pinfunction "DIO5_15") (pintype "bidirectional"))
    )
    (net (code "42") (name "Net-(U$1-RESET)") (class "Default")
      (node (ref "C11") (pin "1") (pinfunction "1_1") (pintype "passive"))
      (node (ref "S2") (pin "1") (pinfunction "1_1") (pintype "passive"))
      (node (ref "S2") (pin "4") (pinfunction "1_4") (pintype "passive"))
      (node (ref "U$1") (pin "5") (pinfunction "RESET_5") (pintype "input"))
    )
    (net (code "43") (name "Net-(U$1-RSSI)") (class "Default")
      (node (ref "R14") (pin "2") (pinfunction "2_2") (pintype "passive"))
      (node (ref "U$1") (pin "6") (pinfunction "RSSI_6") (pintype "bidirectional"))
    )
    (net (code "44") (name "Net-(U$3-K)") (class "Default")
      (node (ref "D2") (pin "A") (pinfunction "A_A") (pintype "passive"))
      (node (ref "U$3") (pin "P$1") (pinfunction "K_P$1") (pintype "passive"))
    )
    (net (code "45") (name "Net-(U$11-CARD_DETECT)") (class "Default")
      (node (ref "R17") (pin "2") (pinfunction "2_2") (pintype "passive"))
      (node (ref "U$11") (pin "DETECT") (pinfunction "CARD_DETECT_DETECT") (pintype "passive"))
    )
    (net (code "46") (name "Net-(U2-BOOT0)") (class "Default")
      (node (ref "R20") (pin "2") (pinfunction "2_2") (pintype "passive"))
      (node (ref "U2") (pin "60") (pinfunction "BOOT0_60") (pintype "input"))
    )
    (net (code "47") (name "Net-(U2-PB3)") (class "Default")
      (node (ref "R27") (pin "2") (pinfunction "2_2") (pintype "passive"))
      (node (ref "U2") (pin "55") (pinfunction "PB3_55") (pintype "bidirectional"))
    )
    (net (code "48") (name "Net-(U2-PB5)") (class "Default")
      (node (ref "R28") (pin "2") (pinfunction "2_2") (pintype "passive"))
      (node (ref "U2") (pin "57") (pinfunction "PB5_57") (pintype "bidirectional"))
    )
    (net (code "49") (name "Net-(U2-PB7)") (class "Default")
      (node (ref "R29") (pin "2") (pinfunction "2_2") (pintype "passive"))
      (node (ref "U2") (pin "59") (pinfunction "PB7_59") (pintype "bidirectional"))
    )
    (net (code "50") (name "Net-(U2-PH1-OSC_OUT)") (class "Default")
      (node (ref "C9") (pin "2") (pinfunction "2_2") (pintype "passive"))
      (node (ref "Q1") (pin "1") (pinfunction "1_1") (pintype "passive"))
      (node (ref "U2") (pin "6") (pinfunction "PH1-OSC_OUT_6") (pintype "bidirectional"))
    )
    (net (code "51") (name "Net-(U2-VBAT)") (class "Default")
      (node (ref "C3") (pin "1") (pinfunction "1_1") (pintype "passive"))
      (node (ref "U2") (pin "1") (pinfunction "VBAT_1") (pintype "power_in"))
    )
    (net (code "52") (name "Net-(U2-VCAP_1)") (class "Default")
      (node (ref "C18") (pin "1") (pinfunction "1_1") (pintype "passive"))
      (node (ref "U2") (pin "30") (pinfunction "VCAP_1_30") (pintype "power_in"))
    )
    (net (code "53") (name "Net-(U3-REGOUT)") (class "Default")
      (node (ref "C22") (pin "1") (pinfunction "1_1") (pintype "passive"))
      (node (ref "U3") (pin "10") (pinfunction "REGOUT_10") (pintype "bidirectional"))
    )
    (net (code "54") (name "Net-(U17-+IN)") (class "Default")
      (node (ref "C25") (pin "2") (pinfunction "2_2") (pintype "passive"))
      (node (ref "C27") (pin "1") (pinfunction "1_1") (pintype "passive"))
      (node (ref "R8") (pin "2") (pinfunction "2_2") (pintype "passive"))
      (node (ref "U17") (pin "4") (pinfunction "+IN_4") (pintype "input"))
    )
    (net (code "55") (name "Net-(U17--IN)") (class "Default")
      (node (ref "C25") (pin "1") (pinfunction "1_1") (pintype "passive"))
      (node (ref "C26") (pin "2") (pinfunction "2_2") (pintype "passive"))
      (node (ref "R9") (pin "2") (pinfunction "2_2") (pintype "passive"))
      (node (ref "U17") (pin "1") (pinfunction "-IN_1") (pintype "input"))
    )
    (net (code "56") (name "Net-(U17-RG)") (class "Default")
      (node (ref "R10") (pin "1") (pinfunction "1_1") (pintype "passive"))
      (node (ref "U17") (pin "3") (pinfunction "RG_3") (pintype "passive"))
    )
    (net (code "57") (name "Net-(U17-RG_2)") (class "Default")
      (node (ref "R10") (pin "2") (pinfunction "2_2") (pintype "passive"))
      (node (ref "U17") (pin "2") (pinfunction "RG_2_2") (pintype "passive"))
    )
    (net (code "58") (name "Net-(U17-VOUT)") (class "Default")
      (node (ref "R11") (pin "1") (pinfunction "1_1") (pintype "passive"))
      (node (ref "U17") (pin "7") (pinfunction "VOUT_7") (pintype "output"))
    )
    (net (code "59") (name "SDIO_CK") (class "Default")
      (node (ref "U$11") (pin "PIN5") (pinfunction "SCLK_PIN5") (pintype "input"))
      (node (ref "U2") (pin "28") (pinfunction "PB2_28") (pintype "bidirectional"))
    )
    (net (code "60") (name "SDIO_CMD") (class "Default")
      (node (ref "R19") (pin "1") (pinfunction "1_1") (pintype "passive"))
      (node (ref "U$11") (pin "PIN3") (pinfunction "DATA_IN_PIN3") (pintype "input"))
      (node (ref "U2") (pin "54") (pinfunction "PD2_54") (pintype "bidirectional"))
    )
    (net (code "61") (name "SDIO_D0") (class "Default")
      (node (ref "R18") (pin "1") (pinfunction "1_1") (pintype "passive"))
      (node (ref "U$11") (pin "PIN7") (pinfunction "DATA_OUT_PIN7") (pintype "output"))
      (node (ref "U2") (pin "39") (pinfunction "PC8_39") (pintype "bidirectional"))
    )
    (net (code "62") (name "SDIO_D1") (class "Default")
      (node (ref "R31") (pin "1") (pinfunction "1_1") (pintype "passive"))
      (node (ref "U$11") (pin "PIN8") (pinfunction "DAT1_PIN8") (pintype "bidirectional"))
      (node (ref "U2") (pin "26") (pinfunction "PB0_26") (pintype "bidirectional"))
    )
    (net (code "63") (name "SDIO_D2") (class "Default")
      (node (ref "R32") (pin "1") (pinfunction "1_1") (pintype "passive"))
      (node (ref "U$11") (pin "PIN1") (pinfunction "DAT2_PIN1") (pintype "bidirectional"))
      (node (ref "U2") (pin "27") (pinfunction "PB1_27") (pintype "bidirectional"))
    )
    (net (code "64") (name "SDIO_D3") (class "Default")
      (node (ref "R30") (pin "1") (pinfunction "1_1") (pintype "passive"))
      (node (ref "U$11") (pin "PIN2") (pinfunction "CS_PIN2") (pintype "input"))
      (node (ref "U2") (pin "52") (pinfunction "PC11_52") (pintype "bidirectional"))
    )
    (net (code "65") (name "SD_DETECT") (class "Default")
      (node (ref "C24") (pin "1") (pinfunction "1_1") (pintype "passive"))
      (node (ref "R17") (pin "1") (pinfunction "1_1") (pintype "passive"))
      (node (ref "U2") (pin "38") (pinfunction "PC7_38") (pintype "bidirectional"))
    )
    (net (code "66") (name "SERVO1_PWM") (class "Default")
      (node (ref "U2") (pin "56") (pinfunction "PB4_56") (pintype "bidirectional"))
    )
    (net (code "67") (name "SERVO2_PWM") (class "Default")
      (node (ref "R6") (pin "1") (pinfunction "1_1") (pintype "passive"))
      (node (ref "U2") (pin "61") (pinfunction "PB8_61") (pintype "bidirectional"))
    )
    (net (code "68") (name "SERVO3_PWM") (class "Default")
      (node (ref "R7") (pin "1") (pinfunction "1_1") (pintype "passive"))
      (node (ref "U2") (pin "62") (pinfunction "PB9_62") (pintype "bidirectional"))
    )
    (net (code "69") (name "SWCLK") (class "Default")
      (node (ref "U2") (pin "49") (pinfunction "PA14_49") (pintype "bidirectional"))
      (node (ref "X1") (pin "3") (pinfunction "S_3") (pintype "passive"))
    )
    (net (code "70") (name "SWDIO") (class "Default")
      (node (ref "U2") (pin "46") (pinfunction "PA13_46") (pintype "bidirectional"))
      (node (ref "X1") (pin "4") (pinfunction "S_4") (pintype "passive"))
    )
    (net (code "71") (name "TENSO_ADC") (class "Default")
      (node (ref "C28") (pin "1") (pinfunction "1_1") (pintype "passive"))
      (node (ref "R11") (pin "2") (pinfunction "2_2") (pintype "passive"))
      (node (ref "U2") (pin "8") (pinfunction "PC0_8") (pintype "bidirectional"))
    )
    (net (code "72") (name "TENSO_IN+") (class "Default")
      (node (ref "R8") (pin "1") (pinfunction "1_1") (pintype "passive"))
      (node (ref "X6") (pin "14") (pinfunction "14_14") (pintype "passive"))
    )
    (net (code "73") (name "TENSO_IN-") (class "Default")
      (node (ref "R9") (pin "1") (pinfunction "1_1") (pintype "passive"))
      (node (ref "X6") (pin "15") (pinfunction "15_15") (pintype "passive"))
    )
    (net (code "74") (name "UART_RX") (class "Default")
      (node (ref "U2") (pin "17") (pinfunction "PA3_17") (pintype "bidirectional"))
      (node (ref "X2") (pin "2") (pinfunction "S_2") (pintype "passive"))
    )
    (net (code "75") (name "UART_TX") (class "Default")
      (node (ref "U2") (pin "16") (pinfunction "PA2_16") (pintype "bidirectional"))
      (node (ref "X2") (pin "3") (pinfunction "S_3") (pintype "passive"))
    )
    (net (code "76") (name "XBEE_RX") (class "Default")
      (node (ref "U$1") (pin "2") (pinfunction "DOUT_2") (pintype "output"))
      (node (ref "U2") (pin "43") (pinfunction "PA10_43") (pintype "bidirectional"))
    )
    (net (code "77") (name "XBEE_TX") (class "Default")
      (node (ref "U$1") (pin "3") (pinfunction "DIN_3") (pintype "input"))
      (node (ref "U2") (pin "42") (pinfunction "PA9_42") (pintype "bidirectional"))
    )
    (net (code "78") (name "XBEE_VDD") (class "Default")
      (node (ref "C13") (pin "+") (pinfunction "+_+") (pintype "passive"))
      (node (ref "C30") (pin "1") (pinfunction "1_1") (pintype "passive"))
      (node (ref "IC1") (pin "2") (pinfunction "OUT_2") (pintype "passive"))
      (node (ref "U$1") (pin "1") (pinfunction "VDD_1") (pintype "power_in"))
    )
    (net (code "79") (name "unconnected-(R24-Pad1)") (class "Default")
      (node (ref "R24") (pin "1") (pinfunction "1_1") (pintype "passive"))
    )
    (net (code "80") (name "unconnected-(U$1-CTS-Pad12)") (class "Default")
      (node (ref "U$1") (pin "12") (pinfunction "CTS_12") (pintype "output"))
    )
    (net (code "81") (name "unconnected-(U$1-DIO0-Pad20)") (class "Default")
      (node (ref "U$1") (pin "20") (pinfunction "DIO0_20") (pintype "bidirectional"))
    )
    (net (code "82") (name "unconnected-(U$1-DIO1-Pad19)") (class "Default")
      (node (ref "U$1") (pin "19") (pinfunction "DIO1_19") (pintype "bidirectional"))
    )
    (net (code "83") (name "unconnected-(U$1-DIO2-Pad18)") (class "Default")
      (node (ref "U$1") (pin "18") (pinfunction "DIO2_18") (pintype "bidirectional"))
    )
    (net (code "84") (name "unconnected-(U$1-DIO3-Pad17)") (class "Default")
      (node (ref "U$1") (pin "17") (pinfunction "DIO3_17") (pintype "bidirectional"))
    )
    (net (code "85") (name "unconnected-(U$1-DIO4-Pad11)") (class "Default")
      (node (ref "U$1") (pin "11") (pinfunction "DIO4_11") (pintype "bidirectional"))
    )
    (net (code "86") (name "unconnected-(U$1-DIO9-Pad13)") (class "Default")
      (node (ref "U$1") (pin "13") (pinfunction "DIO9_13") (pintype "bidirectional"))
    )
    (net (code "87") (name "unconnected-(U$1-DIO11-Pad7)") (class "Default")
      (node (ref "U$1") (pin "7") (pinfunction "DIO11_7") (pintype "bidirectional"))
    )
    (net (code "88") (name "unconnected-(U$1-DIO12-Pad4)") (class "Default")
      (node (ref "U$1") (pin "4") (pinfunction "DIO12_4") (pintype "bidirectional"))
    )
    (net (code "89") (name "unconnected-(U$1-DTR-Pad9)") (class "Default")
      (node (ref "U$1") (pin "9") (pinfunction "DTR_9") (pintype "bidirectional"))
    )
    (net (code "90") (name "unconnected-(U$1-RES-Pad8)") (class "Default")
      (node (ref "U$1") (pin "8") (pinfunction "RES_8") (pintype "bidirectional"))
    )
    (net (code "91") (name "unconnected-(U$1-RES-Pad14)") (class "Default")
      (node (ref "U$1") (pin "14") (pinfunction "RES_14") (pintype "bidirectional"))
    )
    (net (code "92") (name "unconnected-(U$1-RTS-Pad16)") (class "Default")
      (node (ref "U$1") (pin "16") (pinfunction "RTS_16") (pintype "input"))
    )
    (net (code "93") (name "unconnected-(U$10-PadP$1)") (class "Default")
      (node (ref "U$10") (pin "P$1") (pinfunction "P$1_P$1") (pintype "bidirectional"))
    )
    (net (code "94") (name "unconnected-(U1-VREF-Pad5)") (class "Default")
      (node (ref "U1") (pin "5") (pinfunction "VREF_5") (pintype "output"))
    )
    (net (code "95") (name "unconnected-(U2-PA0-Pad14)") (class "Default")
      (node (ref "U2") (pin "14") (pinfunction "PA0_14") (pintype "bidirectional"))
    )
    (net (code "96") (name "unconnected-(U2-PA1-Pad15)") (class "Default")
      (node (ref "U2") (pin "15") (pinfunction "PA1_15") (pintype "bidirectional"))
    )
    (net (code "97") (name "unconnected-(U2-PA8-Pad41)") (class "Default")
      (node (ref "U2") (pin "41") (pinfunction "PA8_41") (pintype "bidirectional"))
    )
    (net (code "98") (name "unconnected-(U2-PA15-Pad50)") (class "Default")
      (node (ref "U2") (pin "50") (pinfunction "PA15_50") (pintype "bidirectional"))
    )
    (net (code "99") (name "unconnected-(U2-PB10-Pad29)") (class "Default")
      (node (ref "U2") (pin "29") (pinfunction "PB10_29") (pintype "bidirectional"))
    )
    (net (code "100") (name "unconnected-(U2-PC1-Pad9)") (class "Default")
      (node (ref "U2") (pin "9") (pinfunction "PC1_9") (pintype "bidirectional"))
    )
    (net (code "101") (name "unconnected-(U2-PC2-Pad10)") (class "Default")
      (node (ref "U2") (pin "10") (pinfunction "PC2_10") (pintype "bidirectional"))
    )
    (net (code "102") (name "unconnected-(U2-PC3-Pad11)") (class "Default")
      (node (ref "U2") (pin "11") (pinfunction "PC3_11") (pintype "bidirectional"))
    )
    (net (code "103") (name "unconnected-(U2-PC4-Pad24)") (class "Default")
      (node (ref "U2") (pin "24") (pinfunction "PC4_24") (pintype "bidirectional"))
    )
    (net (code "104") (name "unconnected-(U2-PC5-Pad25)") (class "Default")
      (node (ref "U2") (pin "25") (pinfunction "PC5_25") (pintype "bidirectional"))
    )
    (net (code "105") (name "unconnected-(U2-PC9-Pad40)") (class "Default")
      (node (ref "U2") (pin "40") (pinfunction "PC9_40") (pintype "bidirectional"))
    )
    (net (code "106") (name "unconnected-(U2-PC13-Pad2)") (class "Default")
      (node (ref "U2") (pin "2") (pinfunction "PC13_2") (pintype "bidirectional"))
    )
    (net (code "107") (name "unconnected-(U2-PC14-OSC32_IN-Pad3)") (class "Default")
      (node (ref "U2") (pin "3") (pinfunction "PC14-OSC32_IN_3") (pintype "bidirectional"))
    )
    (net (code "108") (name "unconnected-(U2-PC15-OSC32_OUT-Pad4)") (class "Default")
      (node (ref "U2") (pin "4") (pinfunction "PC15-OSC32_OUT_4") (pintype "bidirectional"))
    )
    (net (code "109") (name "unconnected-(U3-AUX_CL-Pad7)") (class "Default")
      (node (ref "U3") (pin "7") (pinfunction "AUX_CL_7") (pintype "bidirectional"))
    )
    (net (code "110") (name "unconnected-(U3-AUX_DA-Pad21)") (class "Default")
      (node (ref "U3") (pin "21") (pinfunction "AUX_DA_21") (pintype "bidirectional"))
    )
    (net (code "111") (name "unconnected-(U3-NC-Pad2)") (class "Default")
      (node (ref "U3") (pin "2") (pinfunction "NC_2") (pintype "bidirectional"))
    )
    (net (code "112") (name "unconnected-(U3-NC-Pad3)") (class "Default")
      (node (ref "U3") (pin "3") (pinfunction "NC_3") (pintype "bidirectional"))
    )
    (net (code "113") (name "unconnected-(U3-NC-Pad4)") (class "Default")
      (node (ref "U3") (pin "4") (pinfunction "NC_4") (pintype "bidirectional"))
    )
    (net (code "114") (name "unconnected-(U3-NC-Pad5)") (class "Default")
      (node (ref "U3") (pin "5") (pinfunction "NC_5") (pintype "bidirectional"))
    )
    (net (code "115") (name "unconnected-(U3-NC-Pad6)") (class "Default")
      (node (ref "U3") (pin "6") (pinfunction "NC_6") (pintype "bidirectional"))
    )
    (net (code "116") (name "unconnected-(U3-NC-Pad14)") (class "Default")
      (node (ref "U3") (pin "14") (pinfunction "NC_14") (pintype "bidirectional"))
    )
    (net (code "117") (name "unconnected-(U3-NC-Pad15)") (class "Default")
      (node (ref "U3") (pin "15") (pinfunction "NC_15") (pintype "bidirectional"))
    )
    (net (code "118") (name "unconnected-(U3-NC-Pad16)") (class "Default")
      (node (ref "U3") (pin "16") (pinfunction "NC_16") (pintype "bidirectional"))
    )
    (net (code "119") (name "unconnected-(U3-NC-Pad17)") (class "Default")
      (node (ref "U3") (pin "17") (pinfunction "NC_17") (pintype "bidirectional"))
    )
    (net (code "120") (name "unconnected-(U3-RESV-Pad19)") (class "Default")
      (node (ref "U3") (pin "19") (pinfunction "RESV_19") (pintype "bidirectional"))
    )
    (net (code "121") (name "unconnected-(X8D-S-Pad4)") (class "Default")
      (node (ref "X8") (pin "4") (pinfunction "S_4") (pintype "passive"))
    )
  )
)
